# DIPSY_UL1K16.net
KiCad netlist of a schematic drawn in Altium Designer
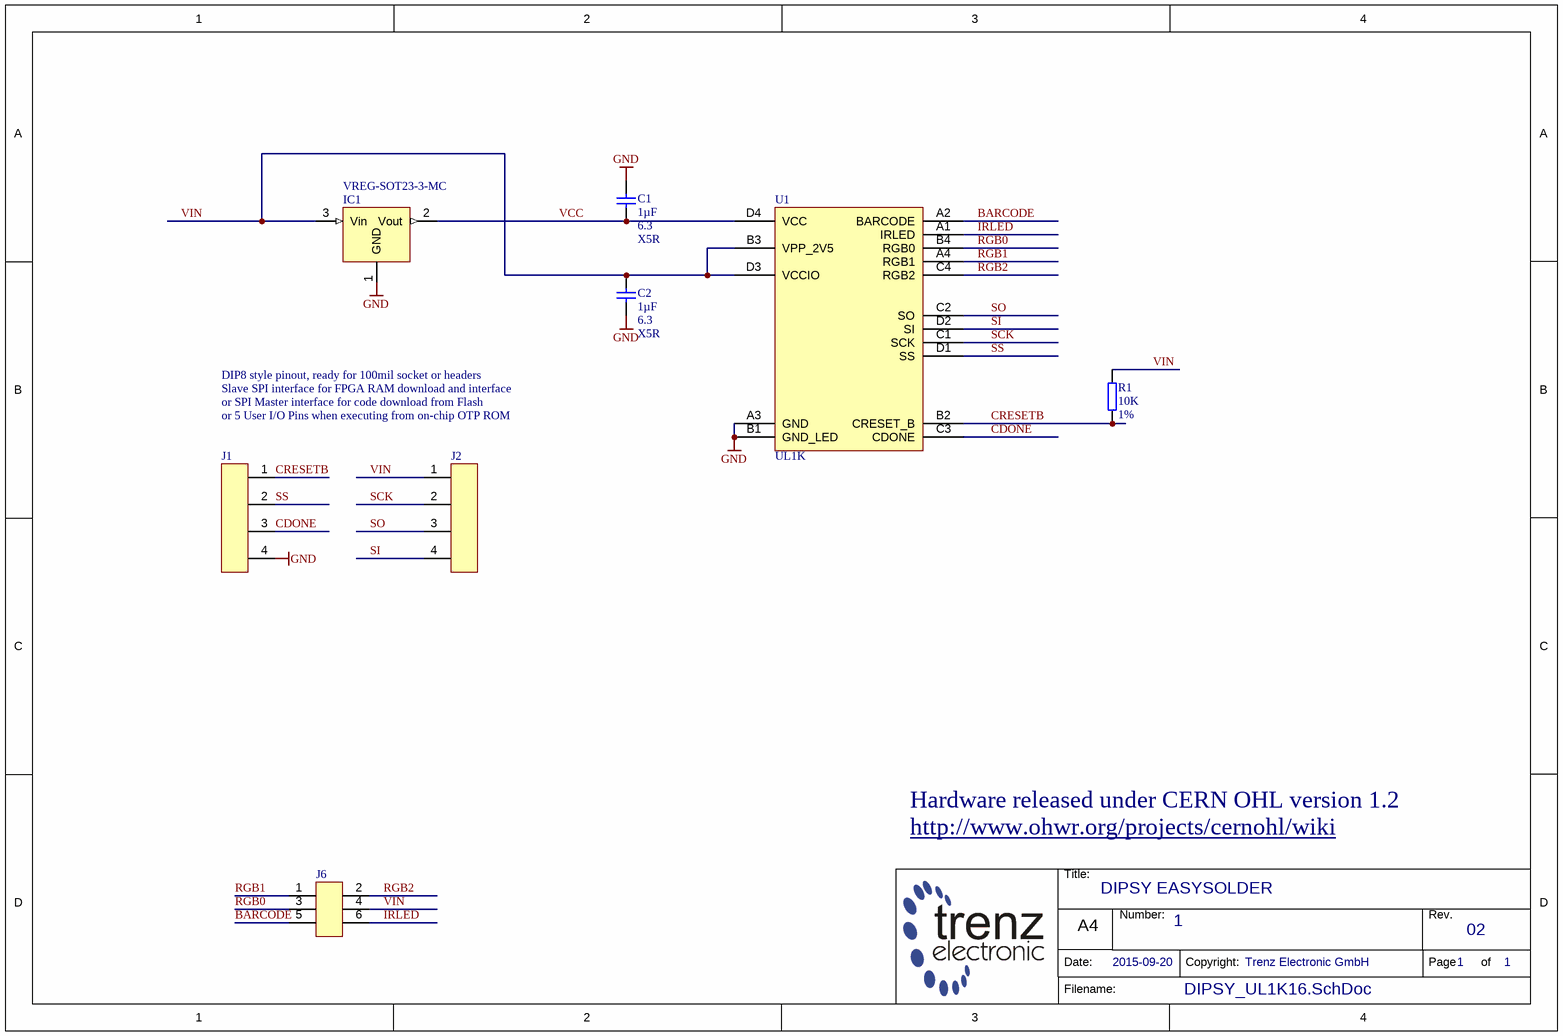
[diagram p0: DIPSY_UL1K16.SchDoc]

(export (version "E")
  (design (tool "Eeschema 10.0.6"))
  (components
    (comp (ref "C1")
      (value "1µF")
      (footprint "CAPC1005X55N")
      (description "KON 1µF 6.3V X5R SMD 10%")
      (fields
        (field (name "VOLTAGE") "6.3")
        (field (name "TECHNOLOGY") "X5R")
        (field (name "TOLERANCE") "10%")
      )
      (libsource (lib "TE") (part "CAP-NP"))
    )
    (comp (ref "C2")
      (value "1µF")
      (footprint "CAPC1005X55N")
      (description "KON 1µF 6.3V X5R SMD 10%")
      (fields
        (field (name "VOLTAGE") "6.3")
        (field (name "TECHNOLOGY") "X5R")
        (field (name "TOLERANCE") "10%")
      )
      (libsource (lib "TE") (part "CAP-NP"))
    )
    (comp (ref "IC1")
      (value "VREG-SOT23-3-MC")
      (footprint "SOT23")
      (libsource (lib "trioflex-cadlib") (part "VREG-SOT23-3-MC"))
    )
    (comp (ref "J1")
      (value "Pin Header 2.54 1Row 4Pins")
      (footprint "STIFTLEISTE2_54 OG 1R-4")
      (description "Stiftleiste gerade 1-reihig, 4pol.")
      (libsource (lib "") (part "CON-4_1"))
    )
    (comp (ref "J2")
      (value "Pin Header 2.54 1Row 4Pins")
      (footprint "STIFTLEISTE2_54 OG 1R-4")
      (description "Stiftleiste gerade 1-reihig, 4pol.")
      (libsource (lib "TE") (part "CON-4"))
    )
    (comp (ref "J6")
      (value "Pin Header 2.54 2Row 6Pins")
      (footprint "STIFTLEISTE2_54 OG 2R-6")
      (description "Stiftleiste gerade 2-reihig, 6pol.")
      (libsource (lib "TE") (part "CON-6"))
    )
    (comp (ref "R1")
      (value "10K")
      (footprint "RESC1005X40N")
      (description "WID SMD 10K 1% 0,063W")
      (fields (field (name "TOLERANCE") "1%"))
      (libsource (lib "TE") (part "RES"))
    )
    (comp (ref "U1")
      (value "UL1K")
      (footprint "BGA16C35P4X4_140X140X100")
      (libsource (lib "Schlib1") (part "UL1K"))
    )
  )
  (nets
    (net (code "1") (name "/BARCODE") (class "Default")
      (node (ref "J6") (pin "5") (pintype "passive"))
      (node (ref "U1") (pin "A2") (pinfunction "BARCODE_A2") (pintype "passive"))
    )
    (net (code "2") (name "/CDONE") (class "Default")
      (node (ref "J1") (pin "3") (pintype "passive"))
      (node (ref "U1") (pin "C3") (pinfunction "CDONE_C3") (pintype "passive"))
    )
    (net (code "3") (name "/CRESETB") (class "Default")
      (node (ref "J1") (pin "1") (pintype "passive"))
      (node (ref "R1") (pin "2") (pinfunction "2_2") (pintype "passive"))
      (node (ref "U1") (pin "B2") (pinfunction "CRESET_B_B2") (pintype "passive"))
    )
    (net (code "4") (name "/IRLED") (class "Default")
      (node (ref "J6") (pin "6") (pintype "passive"))
      (node (ref "U1") (pin "A1") (pinfunction "IRLED_A1") (pintype "passive"))
    )
    (net (code "5") (name "/RGB0") (class "Default")
      (node (ref "J6") (pin "3") (pintype "passive"))
      (node (ref "U1") (pin "B4") (pinfunction "RGB0_B4") (pintype "passive"))
    )
    (net (code "6") (name "/RGB1") (class "Default")
      (node (ref "J6") (pin "1") (pintype "passive"))
      (node (ref "U1") (pin "A4") (pinfunction "RGB1_A4") (pintype "passive"))
    )
    (net (code "7") (name "/RGB2") (class "Default")
      (node (ref "J6") (pin "2") (pintype "passive"))
      (node (ref "U1") (pin "C4") (pinfunction "RGB2_C4") (pintype "passive"))
    )
    (net (code "8") (name "/SCK") (class "Default")
      (node (ref "J2") (pin "2") (pintype "passive"))
      (node (ref "U1") (pin "C1") (pinfunction "SCK_C1") (pintype "passive"))
    )
    (net (code "9") (name "/SI") (class "Default")
      (node (ref "J2") (pin "4") (pintype "passive"))
      (node (ref "U1") (pin "D2") (pinfunction "SI_D2") (pintype "passive"))
    )
    (net (code "10") (name "/SO") (class "Default")
      (node (ref "J2") (pin "3") (pintype "passive"))
      (node (ref "U1") (pin "C2") (pinfunction "SO_C2") (pintype "passive"))
    )
    (net (code "11") (name "/SS") (class "Default")
      (node (ref "J1") (pin "2") (pintype "passive"))
      (node (ref "U1") (pin "D1") (pinfunction "SS_D1") (pintype "passive"))
    )
    (net (code "12") (name "/VCC") (class "Default")
      (node (ref "C1") (pin "2") (pinfunction "2_2") (pintype "passive"))
      (node (ref "IC1") (pin "2") (pinfunction "Vout_2") (pintype "output"))
      (node (ref "U1") (pin "D4") (pinfunction "VCC_D4") (pintype "passive"))
    )
    (net (code "13") (name "/VIN") (class "Default")
      (node (ref "C2") (pin "1") (pinfunction "1_1") (pintype "passive"))
      (node (ref "IC1") (pin "3") (pinfunction "Vin_3") (pintype "input"))
      (node (ref "J2") (pin "1") (pintype "passive"))
      (node (ref "J6") (pin "4") (pintype "passive"))
      (node (ref "R1") (pin "1") (pinfunction "1_1") (pintype "passive"))
      (node (ref "U1") (pin "B3") (pinfunction "VPP_2V5_B3") (pintype "passive"))
      (node (ref "U1") (pin "D3") (pinfunction "VCCIO_D3") (pintype "passive"))
    )
    (net (code "14") (name "GND") (class "Default")
      (node (ref "C1") (pin "1") (pinfunction "1_1") (pintype "passive"))
      (node (ref "C2") (pin "2") (pinfunction "2_2") (pintype "passive"))
      (node (ref "IC1") (pin "1") (pinfunction "GND_1") (pintype "passive"))
      (node (ref "J1") (pin "4") (pintype "passive"))
      (node (ref "U1") (pin "A3") (pinfunction "GND_A3") (pintype "passive"))
      (node (ref "U1") (pin "B1") (pinfunction "GND_LED_B1") (pintype "passive"))
    )
  )
)
